# Minimal-Driver.net
KiCad netlist of a schematic drawn in EAGLE
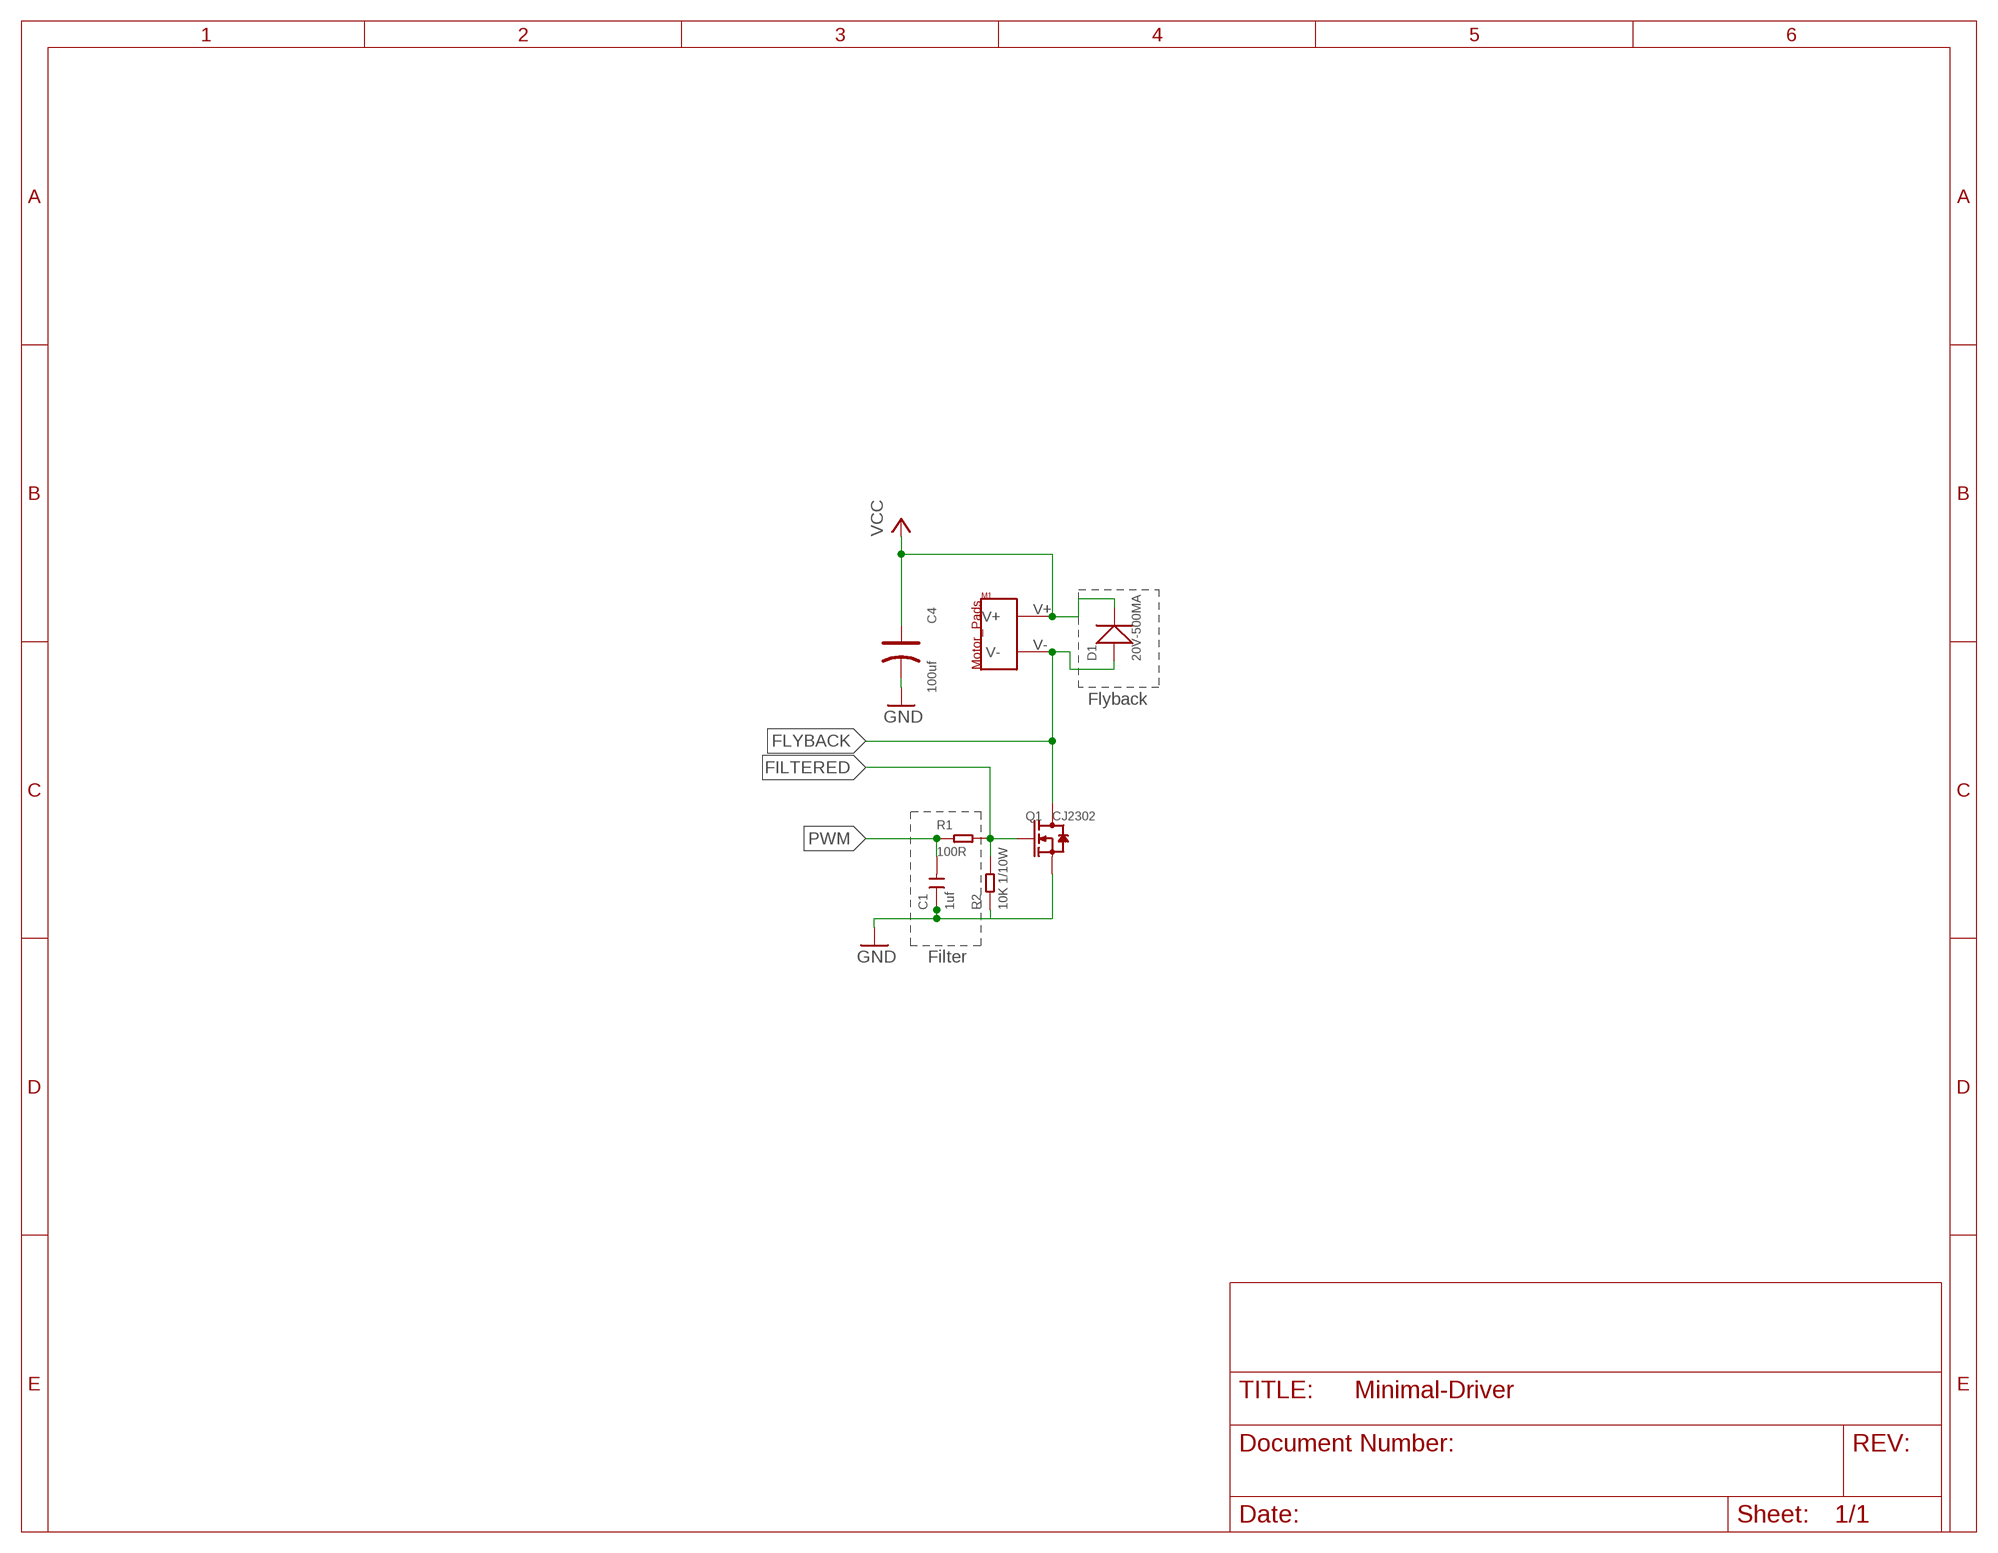
[diagram p0: schematic, sheet 1]

(export (version "E")
  (design (tool "Eeschema 10.0.6"))
  (components
    (comp (ref "C1")
      (value "1uf")
      (footprint "eagle-import:C0402")
      (fields (field (name "MPN") "CC0402KRX5R6BB105"))
      (libsource (lib "eagle-import") (part "CERAMIC-1UF-10V-10%-X5R(0402)"))
    )
    (comp (ref "C4")
      (value "100uf")
      (footprint "eagle-import:AVX-B")
      (fields (field (name "MPN") "TAJB107M010#NJ"))
      (libsource (lib "eagle-import") (part "TANTALUM-SMD-100UF-10V(AVX-B)"))
    )
    (comp (ref "D1")
      (value "20V-500MA")
      (footprint "eagle-import:SOD-123")
      (fields (field (name "MPN") "SS0520-7-F"))
      (libsource (lib "eagle-import") (part "SMD-DIODE-SCHOTTKY-20V-500MA(SOD-123)"))
    )
    (comp (ref "M1")
      (value "MOTOR_PADS")
      (footprint "eagle-import:MOTOR_PADS")
      (libsource (lib "eagle-import") (part "MOTOR_PADS"))
    )
    (comp (ref "Q1")
      (value "CJ2302")
      (footprint "eagle-import:SOT-23")
      (libsource (lib "eagle-import") (part "SMD-MOSFET-N-CH-20V-2.1A-CJ2302(SOT-23)"))
    )
    (comp (ref "R1")
      (value "100R")
      (footprint "eagle-import:R0603")
      (fields (field (name "MPN") "RC0603JR-07100RL"))
      (libsource (lib "eagle-import") (part "SMD-RES-100R-5%-1/10W(0603)"))
    )
    (comp (ref "R2")
      (value "10K 1/10W")
      (footprint "eagle-import:R0603")
      (fields (field (name "MPN") "RC0603JR-0710KL"))
      (libsource (lib "eagle-import") (part "SMD-RES-10K-5%-1/10W(0603)"))
    )
  )
  (nets
    (net (code "1") (name "FILTERED") (class "Default")
      (node (ref "Q1") (pin "1") (pinfunction "G_1") (pintype "passive"))
      (node (ref "R1") (pin "2") (pinfunction "2_2") (pintype "passive"))
      (node (ref "R2") (pin "2") (pinfunction "2_2") (pintype "passive"))
    )
    (net (code "2") (name "FLYBACK") (class "Default")
      (node (ref "D1") (pin "+") (pinfunction "+_+") (pintype "passive"))
      (node (ref "M1") (pin "V-") (pinfunction "V-_V-") (pintype "bidirectional"))
      (node (ref "Q1") (pin "3") (pinfunction "D_3") (pintype "passive"))
    )
    (net (code "3") (name "GND") (class "Default")
      (node (ref "C1") (pin "1") (pinfunction "1_1") (pintype "passive"))
      (node (ref "C4") (pin "-") (pinfunction "-_-") (pintype "passive"))
      (node (ref "Q1") (pin "2") (pinfunction "S_2") (pintype "passive"))
      (node (ref "R2") (pin "1") (pinfunction "1_1") (pintype "passive"))
    )
    (net (code "4") (name "PWM") (class "Default")
      (node (ref "C1") (pin "2") (pinfunction "2_2") (pintype "passive"))
      (node (ref "R1") (pin "1") (pinfunction "1_1") (pintype "passive"))
    )
    (net (code "5") (name "VCC") (class "Default")
      (node (ref "C4") (pin "+") (pinfunction "+_+") (pintype "passive"))
      (node (ref "D1") (pin "-") (pinfunction "-_-") (pintype "passive"))
      (node (ref "M1") (pin "V+") (pinfunction "V+_V+") (pintype "bidirectional"))
    )
  )
)
